# External_Sensor_Board.net
KiCad netlist of a schematic drawn in EAGLE
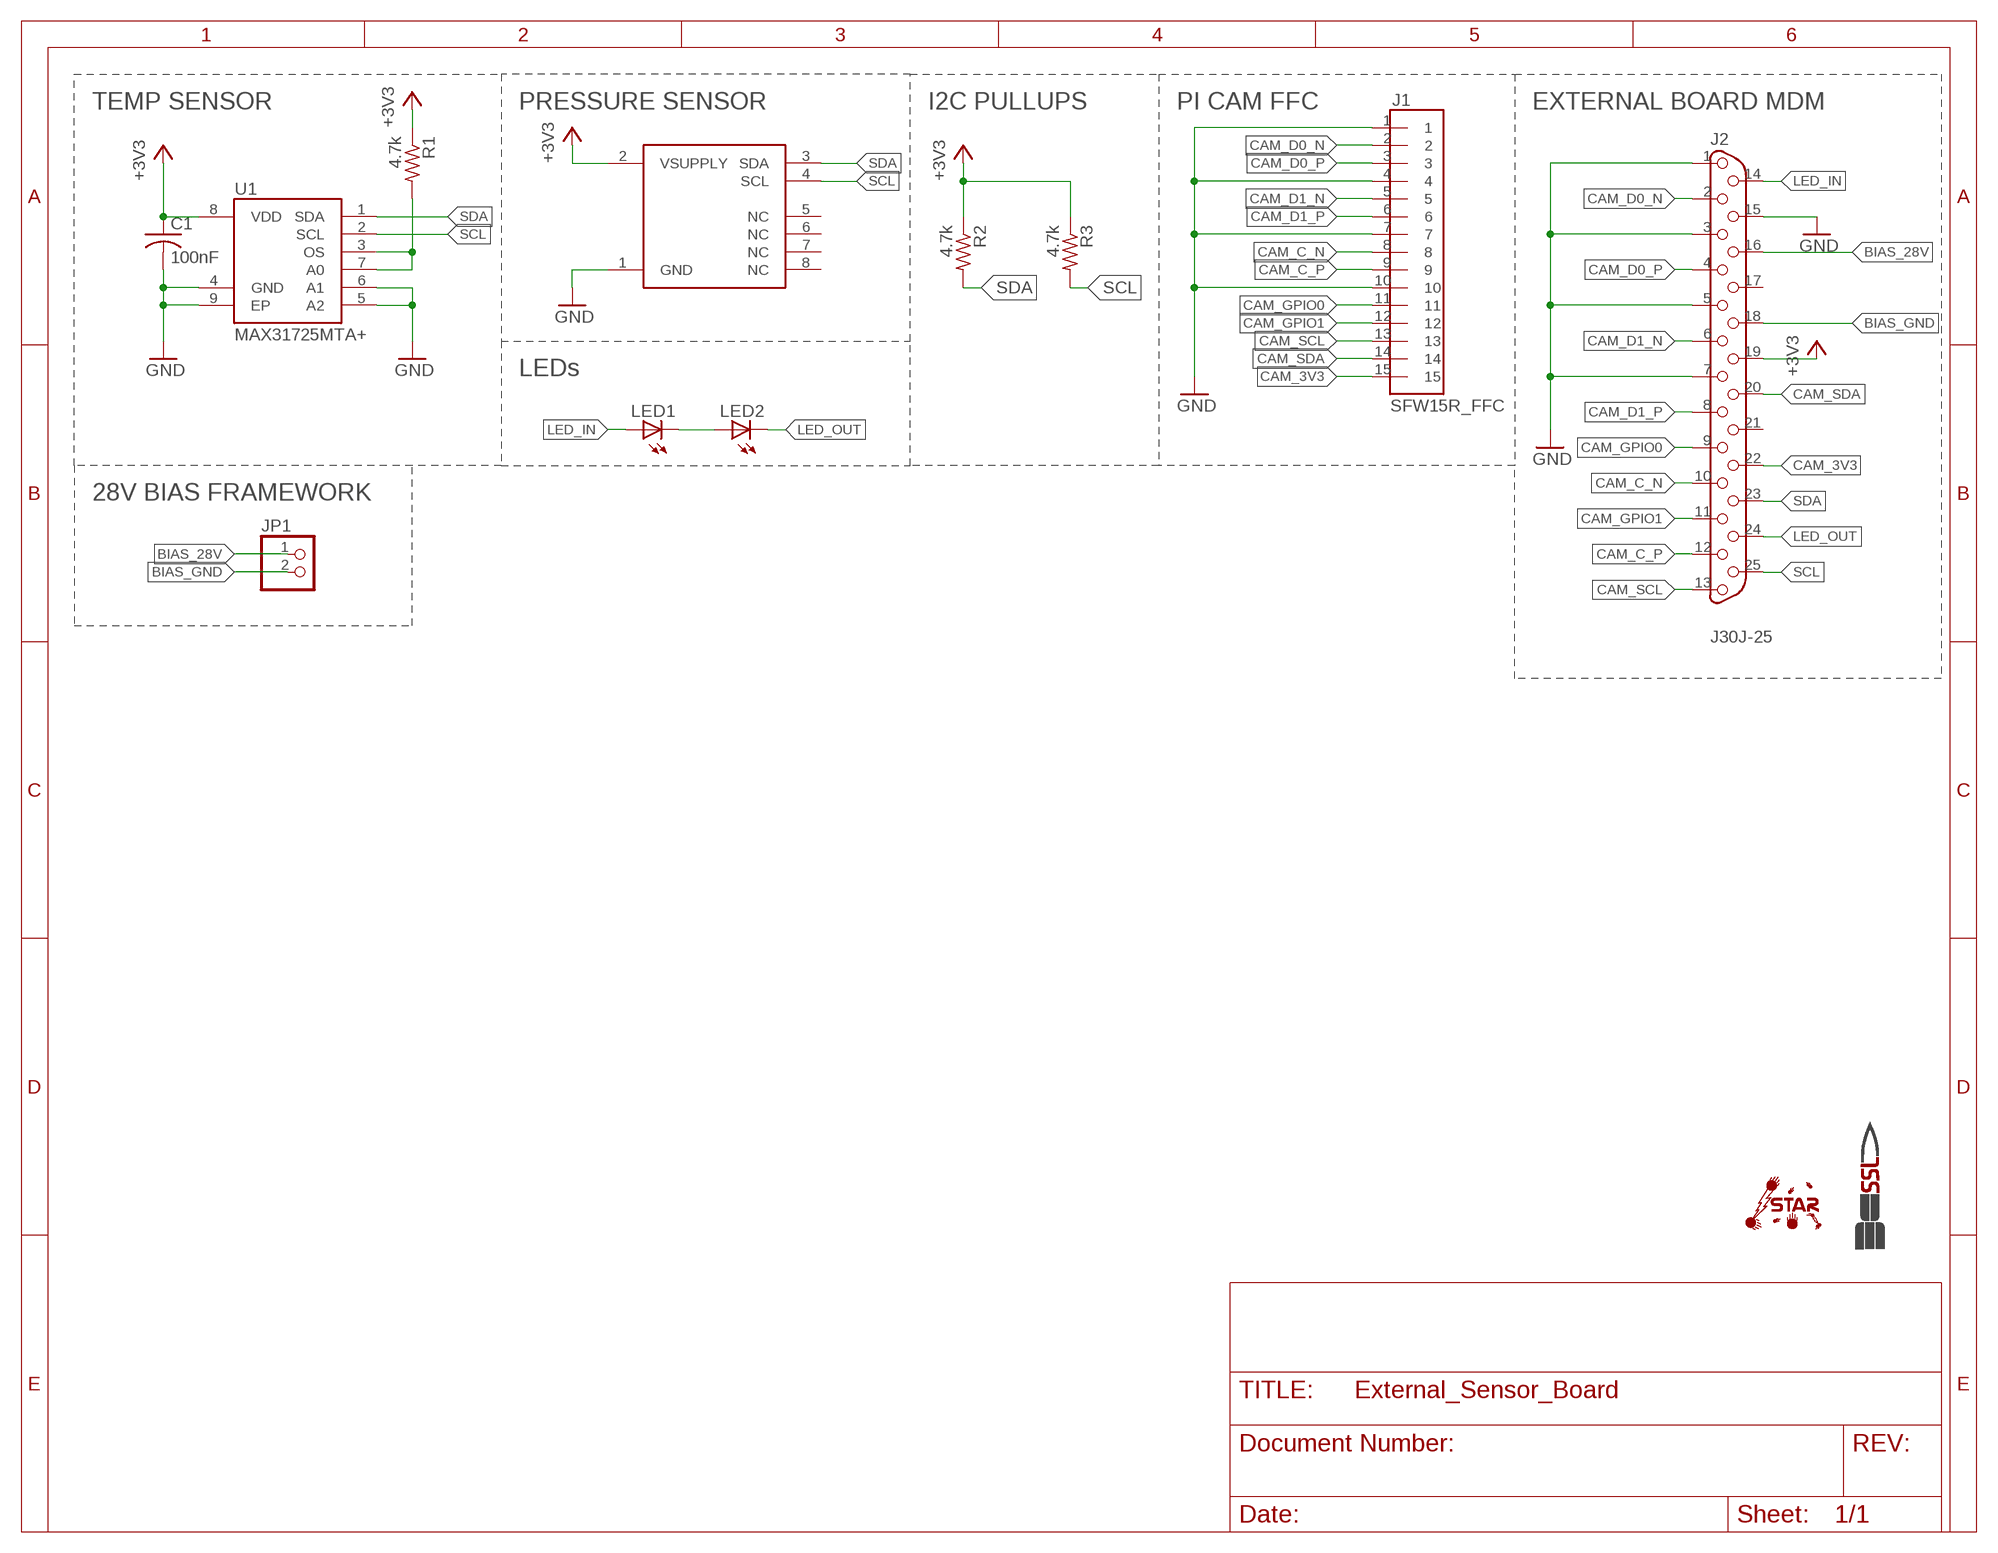
[diagram p0: schematic, sheet 1]

(export (version "E")
  (design (tool "Eeschema 10.0.6"))
  (components
    (comp (ref "C1")
      (value "100nF")
      (footprint "eagle-import:C0603")
      (libsource (lib "eagle-import") (part "C-USC0603"))
    )
    (comp (ref "J1")
      (value "SFW15R_FFC")
      (footprint "eagle-import:AMPHENOL_15_FFC")
      (libsource (lib "eagle-import") (part "SFW15R_FFC"))
    )
    (comp (ref "J2")
      (value "J30J-25")
      (footprint "eagle-import:ZKN-25")
      (libsource (lib "eagle-import") (part "J30J-25"))
    )
    (comp (ref "JP1")
      (value "PINHD-1X2")
      (footprint "eagle-import:1X02")
      (libsource (lib "eagle-import") (part "PINHD-1X2"))
    )
    (comp (ref "LED1")
      (value "LED_1206_NS")
      (footprint "eagle-import:1206_NS")
      (libsource (lib "eagle-import") (part "LED_1206_NS"))
    )
    (comp (ref "LED2")
      (value "LED_1206_NS")
      (footprint "eagle-import:1206_NS")
      (libsource (lib "eagle-import") (part "LED_1206_NS"))
    )
    (comp (ref "R1")
      (value "4.7k")
      (footprint "eagle-import:R0603")
      (libsource (lib "eagle-import") (part "R-US_R0603"))
    )
    (comp (ref "R2")
      (value "4.7k")
      (footprint "eagle-import:R0603")
      (libsource (lib "eagle-import") (part "R-US_R0603"))
    )
    (comp (ref "R3")
      (value "4.7k")
      (footprint "eagle-import:R0603")
      (libsource (lib "eagle-import") (part "R-US_R0603"))
    )
    (comp (ref "U$1")
      (value "SSL.3IN_SILK")
      (footprint "eagle-import:SSL_SILK_.3IN")
      (libsource (lib "eagle-import") (part "SSL.3IN_SILK"))
    )
    (comp (ref "U$2")
      (value "STAR")
      (footprint "eagle-import:STAR_.3IN")
      (libsource (lib "eagle-import") (part "STAR"))
    )
    (comp (ref "U1")
      (value "MAX31725MTA+")
      (footprint "eagle-import:DFN-8")
      (libsource (lib "eagle-import") (part "MAX31725MTA+"))
    )
    (comp (ref "U2")
      (value "SSCMNNN015PA2A3")
      (footprint "eagle-import:HSC-SMT-8")
      (libsource (lib "eagle-import") (part "SSCMNNN015PA2A3"))
    )
  )
  (nets
    (net (code "1") (name "+3V3") (class "Default")
      (node (ref "C1") (pin "1") (pinfunction "1_1") (pintype "passive"))
      (node (ref "J2") (pin "19") (pinfunction "19_19") (pintype "bidirectional"))
      (node (ref "R1") (pin "1") (pinfunction "1_1") (pintype "passive"))
      (node (ref "R2") (pin "1") (pinfunction "1_1") (pintype "passive"))
      (node (ref "R3") (pin "1") (pinfunction "1_1") (pintype "passive"))
      (node (ref "U1") (pin "8") (pinfunction "VDD_8") (pintype "power_in"))
      (node (ref "U2") (pin "2") (pinfunction "VSUPPLY_2") (pintype "power_in"))
    )
    (net (code "2") (name "BIAS_28V") (class "Default")
      (node (ref "J2") (pin "16") (pinfunction "16_16") (pintype "bidirectional"))
      (node (ref "JP1") (pin "1") (pinfunction "1_1") (pintype "passive"))
    )
    (net (code "3") (name "BIAS_GND") (class "Default")
      (node (ref "J2") (pin "18") (pinfunction "18_18") (pintype "bidirectional"))
      (node (ref "JP1") (pin "2") (pinfunction "2_2") (pintype "passive"))
    )
    (net (code "4") (name "CAM_3V3") (class "Default")
      (node (ref "J1") (pin "15") (pinfunction "15_15") (pintype "bidirectional"))
      (node (ref "J2") (pin "22") (pinfunction "22_22") (pintype "bidirectional"))
    )
    (net (code "5") (name "CAM_C_N") (class "Default")
      (node (ref "J1") (pin "8") (pinfunction "8_8") (pintype "bidirectional"))
      (node (ref "J2") (pin "10") (pinfunction "10_10") (pintype "bidirectional"))
    )
    (net (code "6") (name "CAM_C_P") (class "Default")
      (node (ref "J1") (pin "9") (pinfunction "9_9") (pintype "bidirectional"))
      (node (ref "J2") (pin "12") (pinfunction "12_12") (pintype "bidirectional"))
    )
    (net (code "7") (name "CAM_D0_N") (class "Default")
      (node (ref "J1") (pin "2") (pinfunction "2_2") (pintype "bidirectional"))
      (node (ref "J2") (pin "2") (pinfunction "2_2") (pintype "bidirectional"))
    )
    (net (code "8") (name "CAM_D0_P") (class "Default")
      (node (ref "J1") (pin "3") (pinfunction "3_3") (pintype "bidirectional"))
      (node (ref "J2") (pin "4") (pinfunction "4_4") (pintype "bidirectional"))
    )
    (net (code "9") (name "CAM_D1_N") (class "Default")
      (node (ref "J1") (pin "5") (pinfunction "5_5") (pintype "bidirectional"))
      (node (ref "J2") (pin "6") (pinfunction "6_6") (pintype "bidirectional"))
    )
    (net (code "10") (name "CAM_D1_P") (class "Default")
      (node (ref "J1") (pin "6") (pinfunction "6_6") (pintype "bidirectional"))
      (node (ref "J2") (pin "8") (pinfunction "8_8") (pintype "bidirectional"))
    )
    (net (code "11") (name "CAM_GPIO0") (class "Default")
      (node (ref "J1") (pin "11") (pinfunction "11_11") (pintype "bidirectional"))
      (node (ref "J2") (pin "9") (pinfunction "9_9") (pintype "bidirectional"))
    )
    (net (code "12") (name "CAM_GPIO1") (class "Default")
      (node (ref "J1") (pin "12") (pinfunction "12_12") (pintype "bidirectional"))
      (node (ref "J2") (pin "11") (pinfunction "11_11") (pintype "bidirectional"))
    )
    (net (code "13") (name "CAM_SCL") (class "Default")
      (node (ref "J1") (pin "13") (pinfunction "13_13") (pintype "bidirectional"))
      (node (ref "J2") (pin "13") (pinfunction "13_13") (pintype "bidirectional"))
    )
    (net (code "14") (name "CAM_SDA") (class "Default")
      (node (ref "J1") (pin "14") (pinfunction "14_14") (pintype "bidirectional"))
      (node (ref "J2") (pin "20") (pinfunction "20_20") (pintype "bidirectional"))
    )
    (net (code "15") (name "GND") (class "Default")
      (node (ref "C1") (pin "2") (pinfunction "2_2") (pintype "passive"))
      (node (ref "J1") (pin "1") (pinfunction "1_1") (pintype "bidirectional"))
      (node (ref "J1") (pin "10") (pinfunction "10_10") (pintype "bidirectional"))
      (node (ref "J1") (pin "4") (pinfunction "4_4") (pintype "bidirectional"))
      (node (ref "J1") (pin "7") (pinfunction "7_7") (pintype "bidirectional"))
      (node (ref "J2") (pin "1") (pinfunction "1_1") (pintype "bidirectional"))
      (node (ref "J2") (pin "15") (pinfunction "15_15") (pintype "bidirectional"))
      (node (ref "J2") (pin "3") (pinfunction "3_3") (pintype "bidirectional"))
      (node (ref "J2") (pin "5") (pinfunction "5_5") (pintype "bidirectional"))
      (node (ref "J2") (pin "7") (pinfunction "7_7") (pintype "bidirectional"))
      (node (ref "U1") (pin "4") (pinfunction "GND_4") (pintype "power_in"))
      (node (ref "U1") (pin "5") (pinfunction "A2_5") (pintype "bidirectional"))
      (node (ref "U1") (pin "6") (pinfunction "A1_6") (pintype "bidirectional"))
      (node (ref "U1") (pin "9") (pinfunction "EP_9") (pintype "power_in"))
      (node (ref "U2") (pin "1") (pinfunction "GND_1") (pintype "power_in"))
    )
    (net (code "16") (name "LED_IN") (class "Default")
      (node (ref "J2") (pin "14") (pinfunction "14_14") (pintype "bidirectional"))
      (node (ref "LED1") (pin "2") (pinfunction "A_2") (pintype "passive"))
    )
    (net (code "17") (name "LED_OUT") (class "Default")
      (node (ref "J2") (pin "24") (pinfunction "24_24") (pintype "bidirectional"))
      (node (ref "LED2") (pin "1") (pinfunction "C_1") (pintype "passive"))
    )
    (net (code "18") (name "Net-(LED1-C)") (class "Default")
      (node (ref "LED1") (pin "1") (pinfunction "C_1") (pintype "passive"))
      (node (ref "LED2") (pin "2") (pinfunction "A_2") (pintype "passive"))
    )
    (net (code "19") (name "Net-(U1-A0)") (class "Default")
      (node (ref "R1") (pin "2") (pinfunction "2_2") (pintype "passive"))
      (node (ref "U1") (pin "3") (pinfunction "OS_3") (pintype "bidirectional"))
      (node (ref "U1") (pin "7") (pinfunction "A0_7") (pintype "bidirectional"))
    )
    (net (code "20") (name "SCL") (class "Default")
      (node (ref "J2") (pin "25") (pinfunction "25_25") (pintype "bidirectional"))
      (node (ref "R3") (pin "2") (pinfunction "2_2") (pintype "passive"))
      (node (ref "U1") (pin "2") (pinfunction "SCL_2") (pintype "bidirectional"))
      (node (ref "U2") (pin "4") (pinfunction "SCL_4") (pintype "bidirectional"))
    )
    (net (code "21") (name "SDA") (class "Default")
      (node (ref "J2") (pin "23") (pinfunction "23_23") (pintype "bidirectional"))
      (node (ref "R2") (pin "2") (pinfunction "2_2") (pintype "passive"))
      (node (ref "U1") (pin "1") (pinfunction "SDA_1") (pintype "bidirectional"))
      (node (ref "U2") (pin "3") (pinfunction "SDA_3") (pintype "bidirectional"))
    )
    (net (code "22") (name "unconnected-(J2-Pad17)") (class "Default")
      (node (ref "J2") (pin "17") (pinfunction "17_17") (pintype "bidirectional"))
    )
    (net (code "23") (name "unconnected-(J2-Pad21)") (class "Default")
      (node (ref "J2") (pin "21") (pinfunction "21_21") (pintype "bidirectional"))
    )
    (net (code "24") (name "unconnected-(U2-NC-Pad5)") (class "Default")
      (node (ref "U2") (pin "5") (pinfunction "NC_5") (pintype "no_connect"))
    )
    (net (code "25") (name "unconnected-(U2-NC-Pad6)") (class "Default")
      (node (ref "U2") (pin "6") (pinfunction "NC_6") (pintype "no_connect"))
    )
    (net (code "26") (name "unconnected-(U2-NC-Pad7)") (class "Default")
      (node (ref "U2") (pin "7") (pinfunction "NC_7") (pintype "no_connect"))
    )
    (net (code "27") (name "unconnected-(U2-NC-Pad8)") (class "Default")
      (node (ref "U2") (pin "8") (pinfunction "NC_8") (pintype "no_connect"))
    )
  )
)
